# Main.net
KiCad netlist of a schematic drawn in EAGLE
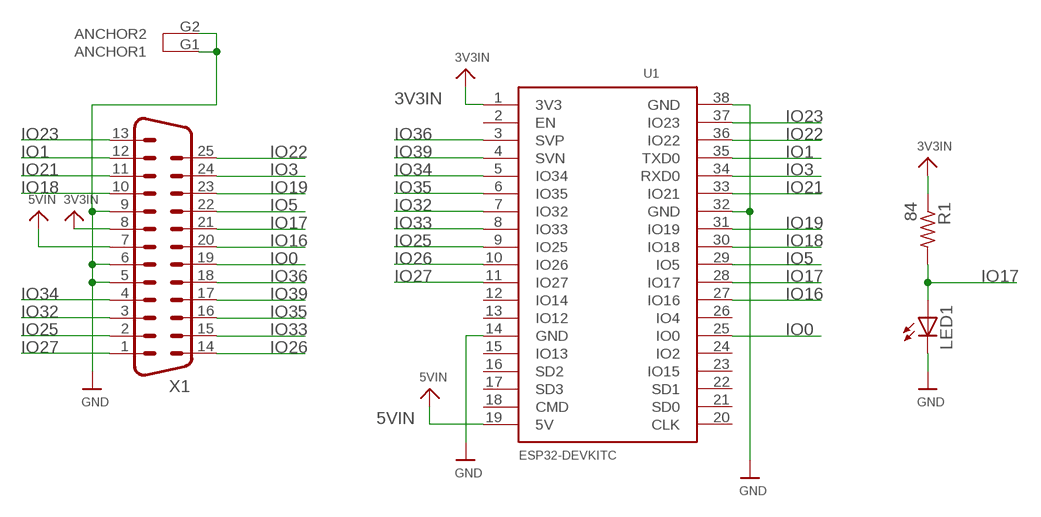
[diagram p0: schematic, sheet 1]

(export (version "E")
  (design (tool "Eeschema 10.0.6"))
  (components
    (comp (ref "LED1")
      (value "LEDCHIPLED_1206")
      (footprint "eagle-import:CHIPLED_1206")
      (libsource (lib "eagle-import") (part "LEDCHIPLED_1206"))
    )
    (comp (ref "R1")
      (value "84")
      (footprint "eagle-import:R1206")
      (libsource (lib "eagle-import") (part "R-US_R1206"))
    )
    (comp (ref "U1")
      (value "ESP32DEVKITC")
      (footprint "eagle-import:ESP32-DEVKITC")
      (libsource (lib "eagle-import") (part "ESP32DEVKITC"))
    )
    (comp (ref "X1")
      (value "DB25_MALEHP")
      (footprint "eagle-import:M25HP")
      (libsource (lib "eagle-import") (part "DB25_MALEHP"))
    )
  )
  (nets
    (net (code "1") (name "/IO0") (class "Default")
      (node (ref "U1") (pin "25") (pinfunction "IO0_25") (pintype "bidirectional"))
      (node (ref "X1") (pin "19") (pinfunction "19_19") (pintype "passive"))
    )
    (net (code "2") (name "/IO1") (class "Default")
      (node (ref "U1") (pin "35") (pinfunction "TXD0_35") (pintype "bidirectional"))
      (node (ref "X1") (pin "12") (pinfunction "12_12") (pintype "passive"))
    )
    (net (code "3") (name "/IO3") (class "Default")
      (node (ref "U1") (pin "34") (pinfunction "RXD0_34") (pintype "bidirectional"))
      (node (ref "X1") (pin "24") (pinfunction "24_24") (pintype "passive"))
    )
    (net (code "4") (name "/IO5") (class "Default")
      (node (ref "U1") (pin "29") (pinfunction "IO5_29") (pintype "bidirectional"))
      (node (ref "X1") (pin "22") (pinfunction "22_22") (pintype "passive"))
    )
    (net (code "5") (name "/IO16") (class "Default")
      (node (ref "U1") (pin "27") (pinfunction "IO16_27") (pintype "bidirectional"))
      (node (ref "X1") (pin "20") (pinfunction "20_20") (pintype "passive"))
    )
    (net (code "6") (name "/IO17") (class "Default")
      (node (ref "LED1") (pin "A") (pinfunction "A_A") (pintype "passive"))
      (node (ref "R1") (pin "2") (pinfunction "2_2") (pintype "passive"))
      (node (ref "U1") (pin "28") (pinfunction "IO17_28") (pintype "bidirectional"))
      (node (ref "X1") (pin "21") (pinfunction "21_21") (pintype "passive"))
    )
    (net (code "7") (name "/IO18") (class "Default")
      (node (ref "U1") (pin "30") (pinfunction "IO18_30") (pintype "bidirectional"))
      (node (ref "X1") (pin "10") (pinfunction "10_10") (pintype "passive"))
    )
    (net (code "8") (name "/IO19") (class "Default")
      (node (ref "U1") (pin "31") (pinfunction "IO19_31") (pintype "bidirectional"))
      (node (ref "X1") (pin "23") (pinfunction "23_23") (pintype "passive"))
    )
    (net (code "9") (name "/IO21") (class "Default")
      (node (ref "U1") (pin "33") (pinfunction "IO21_33") (pintype "bidirectional"))
      (node (ref "X1") (pin "11") (pinfunction "11_11") (pintype "passive"))
    )
    (net (code "10") (name "/IO22") (class "Default")
      (node (ref "U1") (pin "36") (pinfunction "IO22_36") (pintype "bidirectional"))
      (node (ref "X1") (pin "25") (pinfunction "25_25") (pintype "passive"))
    )
    (net (code "11") (name "/IO23") (class "Default")
      (node (ref "U1") (pin "37") (pinfunction "IO23_37") (pintype "bidirectional"))
      (node (ref "X1") (pin "13") (pinfunction "13_13") (pintype "passive"))
    )
    (net (code "12") (name "/IO25") (class "Default")
      (node (ref "U1") (pin "9") (pinfunction "IO25_9") (pintype "bidirectional"))
      (node (ref "X1") (pin "2") (pinfunction "2_2") (pintype "passive"))
    )
    (net (code "13") (name "/IO26") (class "Default")
      (node (ref "U1") (pin "10") (pinfunction "IO26_10") (pintype "bidirectional"))
      (node (ref "X1") (pin "14") (pinfunction "14_14") (pintype "passive"))
    )
    (net (code "14") (name "/IO27") (class "Default")
      (node (ref "U1") (pin "11") (pinfunction "IO27_11") (pintype "bidirectional"))
      (node (ref "X1") (pin "1") (pinfunction "1_1") (pintype "passive"))
    )
    (net (code "15") (name "/IO32") (class "Default")
      (node (ref "U1") (pin "7") (pinfunction "IO32_7") (pintype "bidirectional"))
      (node (ref "X1") (pin "3") (pinfunction "3_3") (pintype "passive"))
    )
    (net (code "16") (name "/IO33") (class "Default")
      (node (ref "U1") (pin "8") (pinfunction "IO33_8") (pintype "bidirectional"))
      (node (ref "X1") (pin "15") (pinfunction "15_15") (pintype "passive"))
    )
    (net (code "17") (name "/IO34") (class "Default")
      (node (ref "U1") (pin "5") (pinfunction "IO34_5") (pintype "bidirectional"))
      (node (ref "X1") (pin "4") (pinfunction "4_4") (pintype "passive"))
    )
    (net (code "18") (name "/IO35") (class "Default")
      (node (ref "U1") (pin "6") (pinfunction "IO35_6") (pintype "bidirectional"))
      (node (ref "X1") (pin "16") (pinfunction "16_16") (pintype "passive"))
    )
    (net (code "19") (name "/IO36") (class "Default")
      (node (ref "U1") (pin "3") (pinfunction "SVP_3") (pintype "bidirectional"))
      (node (ref "X1") (pin "18") (pinfunction "18_18") (pintype "passive"))
    )
    (net (code "20") (name "/IO39") (class "Default")
      (node (ref "U1") (pin "4") (pinfunction "SVN_4") (pintype "bidirectional"))
      (node (ref "X1") (pin "17") (pinfunction "17_17") (pintype "passive"))
    )
    (net (code "21") (name "3V3IN") (class "Default")
      (node (ref "R1") (pin "1") (pinfunction "1_1") (pintype "passive"))
      (node (ref "U1") (pin "1") (pinfunction "3V3_1") (pintype "bidirectional"))
      (node (ref "X1") (pin "8") (pinfunction "8_8") (pintype "passive"))
    )
    (net (code "22") (name "5VIN") (class "Default")
      (node (ref "U1") (pin "19") (pinfunction "5V_19") (pintype "bidirectional"))
      (node (ref "X1") (pin "7") (pinfunction "7_7") (pintype "passive"))
    )
    (net (code "23") (name "GND") (class "Default")
      (node (ref "LED1") (pin "C") (pinfunction "C_C") (pintype "passive"))
      (node (ref "U1") (pin "14") (pinfunction "GND_14") (pintype "bidirectional"))
      (node (ref "U1") (pin "32") (pinfunction "GND_32") (pintype "bidirectional"))
      (node (ref "U1") (pin "38") (pinfunction "GND_38") (pintype "bidirectional"))
      (node (ref "X1") (pin "5") (pinfunction "5_5") (pintype "passive"))
      (node (ref "X1") (pin "6") (pinfunction "6_6") (pintype "passive"))
      (node (ref "X1") (pin "9") (pinfunction "9_9") (pintype "passive"))
      (node (ref "X1") (pin "G1") (pinfunction "ANCHOR1_G1") (pintype "bidirectional"))
      (node (ref "X1") (pin "G2") (pinfunction "ANCHOR2_G2") (pintype "bidirectional"))
    )
    (net (code "24") (name "unconnected-(U1-CLK-Pad20)") (class "Default")
      (node (ref "U1") (pin "20") (pinfunction "CLK_20") (pintype "bidirectional"))
    )
    (net (code "25") (name "unconnected-(U1-CMD-Pad18)") (class "Default")
      (node (ref "U1") (pin "18") (pinfunction "CMD_18") (pintype "bidirectional"))
    )
    (net (code "26") (name "unconnected-(U1-EN-Pad2)") (class "Default")
      (node (ref "U1") (pin "2") (pinfunction "EN_2") (pintype "bidirectional"))
    )
    (net (code "27") (name "unconnected-(U1-IO2-Pad24)") (class "Default")
      (node (ref "U1") (pin "24") (pinfunction "IO2_24") (pintype "bidirectional"))
    )
    (net (code "28") (name "unconnected-(U1-IO4-Pad26)") (class "Default")
      (node (ref "U1") (pin "26") (pinfunction "IO4_26") (pintype "bidirectional"))
    )
    (net (code "29") (name "unconnected-(U1-IO12-Pad13)") (class "Default")
      (node (ref "U1") (pin "13") (pinfunction "IO12_13") (pintype "bidirectional"))
    )
    (net (code "30") (name "unconnected-(U1-IO13-Pad15)") (class "Default")
      (node (ref "U1") (pin "15") (pinfunction "IO13_15") (pintype "bidirectional"))
    )
    (net (code "31") (name "unconnected-(U1-IO14-Pad12)") (class "Default")
      (node (ref "U1") (pin "12") (pinfunction "IO14_12") (pintype "bidirectional"))
    )
    (net (code "32") (name "unconnected-(U1-IO15-Pad23)") (class "Default")
      (node (ref "U1") (pin "23") (pinfunction "IO15_23") (pintype "bidirectional"))
    )
    (net (code "33") (name "unconnected-(U1-SD0-Pad21)") (class "Default")
      (node (ref "U1") (pin "21") (pinfunction "SD0_21") (pintype "bidirectional"))
    )
    (net (code "34") (name "unconnected-(U1-SD1-Pad22)") (class "Default")
      (node (ref "U1") (pin "22") (pinfunction "SD1_22") (pintype "bidirectional"))
    )
    (net (code "35") (name "unconnected-(U1-SD2-Pad16)") (class "Default")
      (node (ref "U1") (pin "16") (pinfunction "SD2_16") (pintype "bidirectional"))
    )
    (net (code "36") (name "unconnected-(U1-SD3-Pad17)") (class "Default")
      (node (ref "U1") (pin "17") (pinfunction "SD3_17") (pintype "bidirectional"))
    )
  )
)
